# DVI-I.net
KiCad netlist of a schematic drawn in Altium Designer
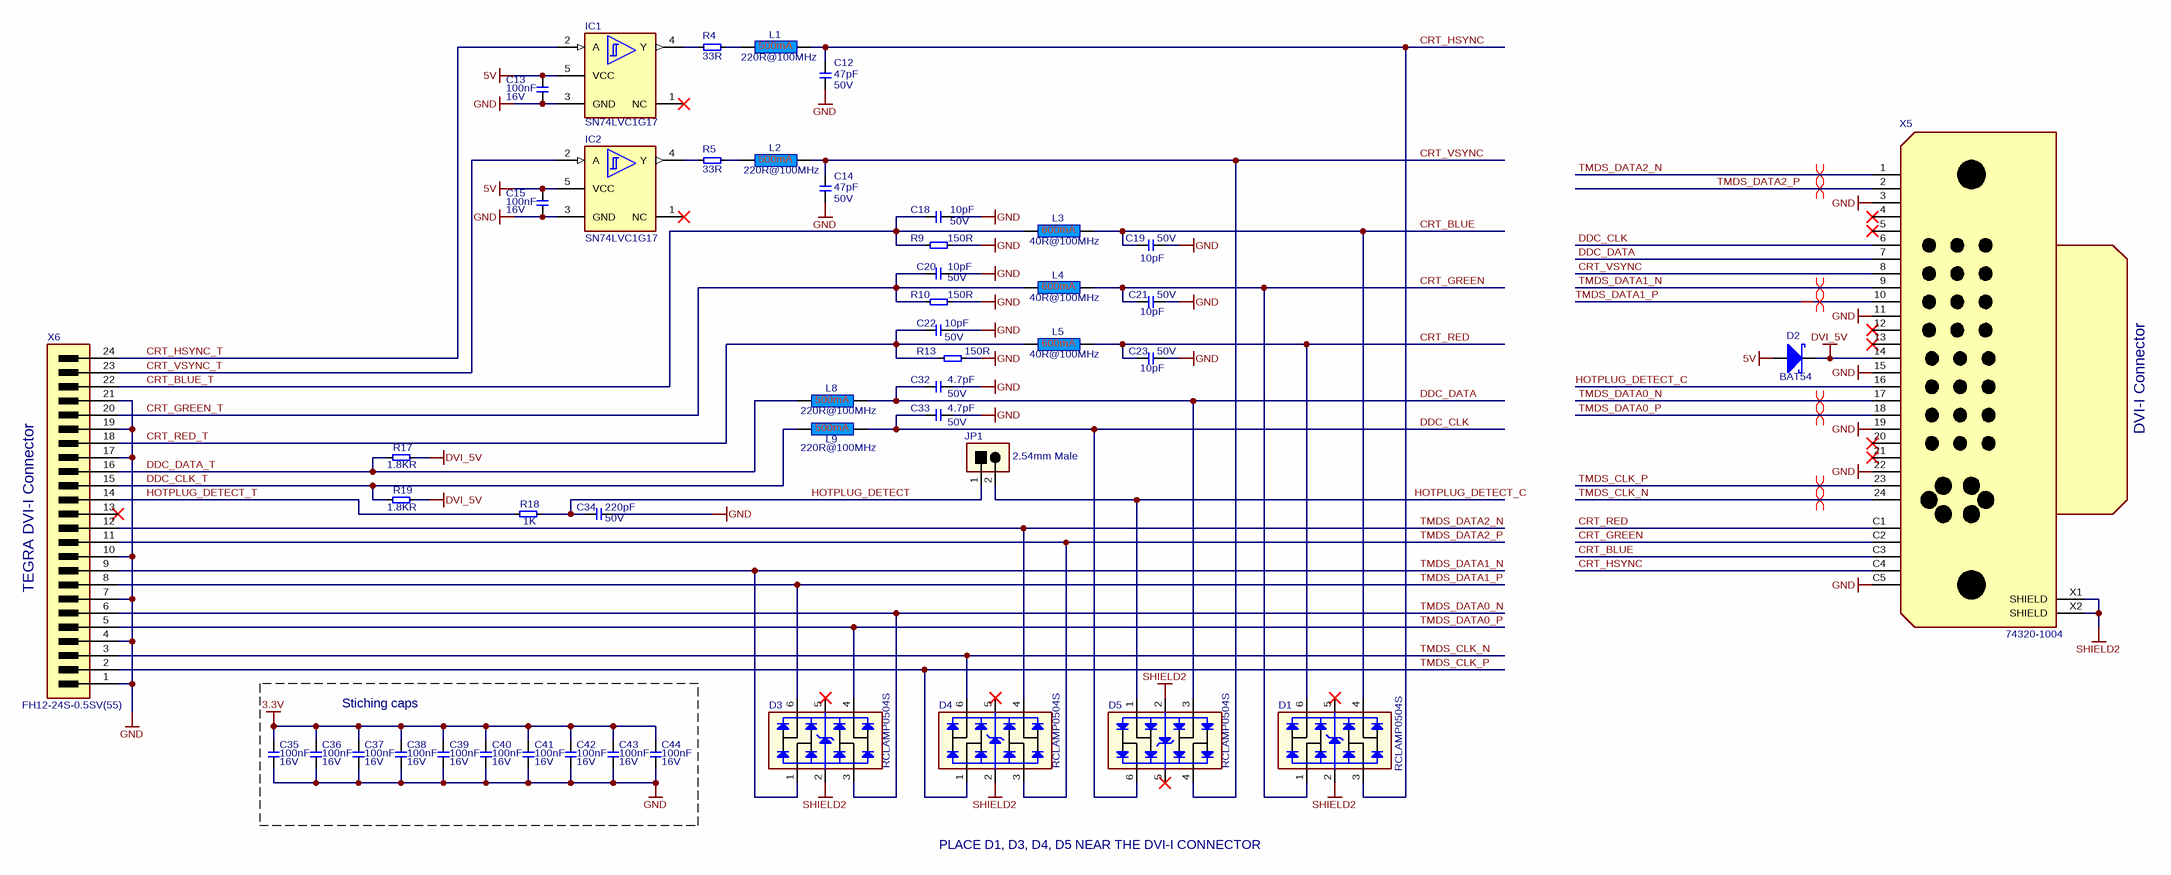
[diagram p0: DVI-I.SchDoc]

(export (version "E")
  (design (tool "Eeschema 10.0.6"))
  (components
    (comp (ref "C12")
      (value "47pF")
      (footprint "T_CAPC0603X33N")
      (description "Capacitor Ceramic NP0 47pF 50V 10% 0603")
      (fields (field (name "TOLERANCE") "10%") (field (name "RATING") "50V"))
      (libsource (lib "Evaluation Board") (part "C-NP0-47pF-50V-10%-0603"))
    )
    (comp (ref "C13")
      (value "100nF")
      (footprint "T_CAPC0603X33N")
      (description "Capacitor Ceramic X7R 100nF 16V 10% 0603")
      (fields (field (name "TOLERANCE") "10%") (field (name "RATING") "16V"))
      (libsource (lib "Evaluation Board") (part "C-X7R-100nF-16V-10%-0603"))
    )
    (comp (ref "C14")
      (value "47pF")
      (footprint "T_CAPC0603X33N")
      (description "Capacitor Ceramic NP0 47pF 50V 10% 0603")
      (fields (field (name "TOLERANCE") "10%") (field (name "RATING") "50V"))
      (libsource (lib "Evaluation Board") (part "C-NP0-47pF-50V-10%-0603"))
    )
    (comp (ref "C15")
      (value "100nF")
      (footprint "T_CAPC0603X33N")
      (description "Capacitor Ceramic X7R 100nF 16V 10% 0603")
      (fields (field (name "TOLERANCE") "10%") (field (name "RATING") "16V"))
      (libsource (lib "Evaluation Board") (part "C-X7R-100nF-16V-10%-0603"))
    )
    (comp (ref "C18")
      (value "10pF")
      (footprint "T_CAPC0603X33N")
      (description "Capacitor Ceramic NP0 10pF 50V 10% 0603")
      (fields (field (name "TOLERANCE") "10%") (field (name "RATING") "50V"))
      (libsource (lib "Evaluation Board") (part "C-NP0-10pF-50V-10%-0603"))
    )
    (comp (ref "C19")
      (value "10pF")
      (footprint "T_CAPC0603X33N")
      (description "Capacitor Ceramic NP0 10pF 50V 10% 0603")
      (fields (field (name "TOLERANCE") "10%") (field (name "RATING") "50V"))
      (libsource (lib "Evaluation Board") (part "C-NP0-10pF-50V-10%-0603"))
    )
    (comp (ref "C20")
      (value "10pF")
      (footprint "T_CAPC0603X33N")
      (description "Capacitor Ceramic NP0 10pF 50V 10% 0603")
      (fields (field (name "TOLERANCE") "10%") (field (name "RATING") "50V"))
      (libsource (lib "Evaluation Board") (part "C-NP0-10pF-50V-10%-0603"))
    )
    (comp (ref "C21")
      (value "10pF")
      (footprint "T_CAPC0603X33N")
      (description "Capacitor Ceramic NP0 10pF 50V 10% 0603")
      (fields (field (name "TOLERANCE") "10%") (field (name "RATING") "50V"))
      (libsource (lib "Evaluation Board") (part "C-NP0-10pF-50V-10%-0603"))
    )
    (comp (ref "C22")
      (value "10pF")
      (footprint "T_CAPC0603X33N")
      (description "Capacitor Ceramic NP0 10pF 50V 10% 0603")
      (fields (field (name "TOLERANCE") "10%") (field (name "RATING") "50V"))
      (libsource (lib "Evaluation Board") (part "C-NP0-10pF-50V-10%-0603"))
    )
    (comp (ref "C23")
      (value "10pF")
      (footprint "T_CAPC0603X33N")
      (description "Capacitor Ceramic NP0 10pF 50V 10% 0603")
      (fields (field (name "TOLERANCE") "10%") (field (name "RATING") "50V"))
      (libsource (lib "Evaluation Board") (part "C-NP0-10pF-50V-10%-0603"))
    )
    (comp (ref "C32")
      (value "4.7pF")
      (footprint "T_CAPC0603X33N")
      (description "Capacitor Ceramic NP0  4.7pF 25V 10% 0603")
      (fields (field (name "TOLERANCE") "10%") (field (name "RATING") "50V"))
      (libsource (lib "Evaluation Board") (part "C-NP0-4.7pF-25V-10%-0603"))
    )
    (comp (ref "C33")
      (value "4.7pF")
      (footprint "T_CAPC0603X33N")
      (description "Capacitor Ceramic NP0  4.7pF 25V 10% 0603")
      (fields (field (name "TOLERANCE") "10%") (field (name "RATING") "50V"))
      (libsource (lib "Evaluation Board") (part "C-NP0-4.7pF-25V-10%-0603"))
    )
    (comp (ref "C34")
      (value "220pF")
      (footprint "T_CAPC0603X33N")
      (description "Capacitor Ceramic X7R 220pF 50V 20% 0603")
      (fields (field (name "TOLERANCE") "20%") (field (name "RATING") "50V"))
      (libsource (lib "Evaluation Board") (part "C-X7R-220pF-50V-20%-0603"))
    )
    (comp (ref "C35")
      (value "100nF")
      (footprint "T_CAPC0603X33N")
      (description "Capacitor Ceramic X7R 100nF 16V 10% 0603")
      (fields (field (name "TOLERANCE") "10%") (field (name "RATING") "16V"))
      (libsource (lib "Evaluation Board") (part "C-X7R-100nF-16V-10%-0603"))
    )
    (comp (ref "C36")
      (value "100nF")
      (footprint "T_CAPC0603X33N")
      (description "Capacitor Ceramic X7R 100nF 16V 10% 0603")
      (fields (field (name "TOLERANCE") "10%") (field (name "RATING") "16V"))
      (libsource (lib "Evaluation Board") (part "C-X7R-100nF-16V-10%-0603"))
    )
    (comp (ref "C37")
      (value "100nF")
      (footprint "T_CAPC0603X33N")
      (description "Capacitor Ceramic X7R 100nF 16V 10% 0603")
      (fields (field (name "TOLERANCE") "10%") (field (name "RATING") "16V"))
      (libsource (lib "Evaluation Board") (part "C-X7R-100nF-16V-10%-0603"))
    )
    (comp (ref "C38")
      (value "100nF")
      (footprint "T_CAPC0603X33N")
      (description "Capacitor Ceramic X7R 100nF 16V 10% 0603")
      (fields (field (name "TOLERANCE") "10%") (field (name "RATING") "16V"))
      (libsource (lib "Evaluation Board") (part "C-X7R-100nF-16V-10%-0603"))
    )
    (comp (ref "C39")
      (value "100nF")
      (footprint "T_CAPC0603X33N")
      (description "Capacitor Ceramic X7R 100nF 16V 10% 0603")
      (fields (field (name "TOLERANCE") "10%") (field (name "RATING") "16V"))
      (libsource (lib "Evaluation Board") (part "C-X7R-100nF-16V-10%-0603"))
    )
    (comp (ref "C40")
      (value "100nF")
      (footprint "T_CAPC0603X33N")
      (description "Capacitor Ceramic X7R 100nF 16V 10% 0603")
      (fields (field (name "TOLERANCE") "10%") (field (name "RATING") "16V"))
      (libsource (lib "Evaluation Board") (part "C-X7R-100nF-16V-10%-0603"))
    )
    (comp (ref "C41")
      (value "100nF")
      (footprint "T_CAPC0603X33N")
      (description "Capacitor Ceramic X7R 100nF 16V 10% 0603")
      (fields (field (name "TOLERANCE") "10%") (field (name "RATING") "16V"))
      (libsource (lib "Evaluation Board") (part "C-X7R-100nF-16V-10%-0603"))
    )
    (comp (ref "C42")
      (value "100nF")
      (footprint "T_CAPC0603X33N")
      (description "Capacitor Ceramic X7R 100nF 16V 10% 0603")
      (fields (field (name "TOLERANCE") "10%") (field (name "RATING") "16V"))
      (libsource (lib "Evaluation Board") (part "C-X7R-100nF-16V-10%-0603"))
    )
    (comp (ref "C43")
      (value "100nF")
      (footprint "T_CAPC0603X33N")
      (description "Capacitor Ceramic X7R 100nF 16V 10% 0603")
      (fields (field (name "TOLERANCE") "10%") (field (name "RATING") "16V"))
      (libsource (lib "Evaluation Board") (part "C-X7R-100nF-16V-10%-0603"))
    )
    (comp (ref "C44")
      (value "100nF")
      (footprint "T_CAPC0603X33N")
      (description "Capacitor Ceramic X7R 100nF 16V 10% 0603")
      (fields (field (name "TOLERANCE") "10%") (field (name "RATING") "16V"))
      (libsource (lib "Evaluation Board") (part "C-X7R-100nF-16V-10%-0603"))
    )
    (comp (ref "D1")
      (value "RCLAMP0504S")
      (footprint "T_SOT95P285X90-6N")
      (description "TVS Array low cap")
      (fields (field (name "MANUFACTURER PART NO.") "RCLAMP0504S"))
      (libsource (lib "") (part "D-Semtech-RClamp0504S_1"))
    )
    (comp (ref "D2")
      (value "BAT54")
      (footprint "SOT95P230X110-3N")
      (description "BAT54 Schottky Diode")
      (fields (field (name "MANUFACTURER PART NO.") "BAT54"))
      (libsource (lib "Evaluation Board") (part "D-Philips-BAT54-Schottky"))
    )
    (comp (ref "D3")
      (value "RCLAMP0504S")
      (footprint "T_SOT95P285X90-6N")
      (description "TVS Array low cap")
      (fields (field (name "MANUFACTURER PART NO.") "RCLAMP0504S"))
      (libsource (lib "") (part "D-Semtech-RClamp0504S_1"))
    )
    (comp (ref "D4")
      (value "RCLAMP0504S")
      (footprint "T_SOT95P285X90-6N")
      (description "TVS Array low cap")
      (fields (field (name "MANUFACTURER PART NO.") "RCLAMP0504S"))
      (libsource (lib "") (part "D-Semtech-RClamp0504S_1"))
    )
    (comp (ref "D5")
      (value "RCLAMP0504S")
      (footprint "T_SOT95P285X90-6N")
      (description "TVS Array low cap")
      (fields (field (name "MANUFACTURER PART NO.") "RCLAMP0504S"))
      (libsource (lib "Evaluation Board") (part "D-Semtech-RClamp0504S"))
    )
    (comp (ref "IC1")
      (value "SN74LVC1G17")
      (footprint "SOT65P210X110-5N")
      (description "Single Schmitt-Trigger Buffer")
      (fields (field (name "MANUFACTURER PART NO.") "SN74LVC1G17"))
      (libsource (lib "Evaluation Board") (part "IC-TI-SN74LVC1G17"))
    )
    (comp (ref "IC2")
      (value "SN74LVC1G17")
      (footprint "SOT65P210X110-5N")
      (description "Single Schmitt-Trigger Buffer")
      (fields (field (name "MANUFACTURER PART NO.") "SN74LVC1G17"))
      (libsource (lib "Evaluation Board") (part "IC-TI-SN74LVC1G17"))
    )
    (comp (ref "JP1")
      (value "TSW-101-07-G-D")
      (footprint "T_Samtec_TSW-101-07-G-D")
      (description "Header male, 1x2 Pins, 2.54 mm pitch")
      (libsource (lib "Evaluation Board") (part "CON-Samtec-TSW-101-07-G-D"))
    )
    (comp (ref "L1")
      (value "220R@100MHz")
      (footprint "INDC1608X95N")
      (description "220R@100MHz 500mA EMI FILTER")
      (fields (field (name "TOLERANCE") "25%"))
      (libsource (lib "Evaluation Board") (part "L-220R@100MHz-500mA-25%-0603"))
    )
    (comp (ref "L2")
      (value "220R@100MHz")
      (footprint "INDC1608X95N")
      (description "220R@100MHz 500mA EMI FILTER")
      (fields (field (name "TOLERANCE") "25%"))
      (libsource (lib "Evaluation Board") (part "L-220R@100MHz-500mA-25%-0603"))
    )
    (comp (ref "L3")
      (value "40R@100MHz")
      (footprint "INDC1608X95N")
      (description "40R@100MHz 600mA EMI FILTER")
      (fields (field (name "TOLERANCE") "25%") (field (name "MANUFACTURER PART NO.") "MMZ1608S400A"))
      (libsource (lib "Evaluation Board") (part "L-TDK-MMZ1608S400A-40R@100MHz-600mA-25%-0603"))
    )
    (comp (ref "L4")
      (value "40R@100MHz")
      (footprint "INDC1608X95N")
      (description "40R@100MHz 600mA EMI FILTER")
      (fields (field (name "TOLERANCE") "25%") (field (name "MANUFACTURER PART NO.") "MMZ1608S400A"))
      (libsource (lib "Evaluation Board") (part "L-TDK-MMZ1608S400A-40R@100MHz-600mA-25%-0603"))
    )
    (comp (ref "L5")
      (value "40R@100MHz")
      (footprint "INDC1608X95N")
      (description "40R@100MHz 600mA EMI FILTER")
      (fields (field (name "TOLERANCE") "25%") (field (name "MANUFACTURER PART NO.") "MMZ1608S400A"))
      (libsource (lib "Evaluation Board") (part "L-TDK-MMZ1608S400A-40R@100MHz-600mA-25%-0603"))
    )
    (comp (ref "L8")
      (value "220R@100MHz")
      (footprint "INDC1608X95N")
      (description "220R@100MHz 500mA EMI FILTER")
      (fields (field (name "TOLERANCE") "25%"))
      (libsource (lib "Evaluation Board") (part "L-220R@100MHz-500mA-25%-0603"))
    )
    (comp (ref "L9")
      (value "220R@100MHz")
      (footprint "INDC1608X95N")
      (description "220R@100MHz 500mA EMI FILTER")
      (fields (field (name "TOLERANCE") "25%"))
      (libsource (lib "Evaluation Board") (part "L-220R@100MHz-500mA-25%-0603"))
    )
    (comp (ref "R4")
      (value "33R")
      (footprint "t_RESC0603X30N")
      (description "Resistor 33 ohm 63mW 5% 0603")
      (fields (field (name "TOLERANCE") "5%"))
      (libsource (lib "Evaluation Board") (part "R-33R-63mW-5%-0603"))
    )
    (comp (ref "R5")
      (value "33R")
      (footprint "t_RESC0603X30N")
      (description "Resistor 33 ohm 63mW 5% 0603")
      (fields (field (name "TOLERANCE") "5%"))
      (libsource (lib "Evaluation Board") (part "R-33R-63mW-5%-0603"))
    )
    (comp (ref "R9")
      (value "150R")
      (footprint "t_RESC0603X30N")
      (description "Resistor 150 ohm 63mW 1% 0603")
      (fields (field (name "TOLERANCE") "1%"))
      (libsource (lib "Evaluation Board") (part "R-150R-63mW-1%-0603"))
    )
    (comp (ref "R10")
      (value "150R")
      (footprint "t_RESC0603X30N")
      (description "Resistor 150 ohm 63mW 1% 0603")
      (fields (field (name "TOLERANCE") "1%"))
      (libsource (lib "Evaluation Board") (part "R-150R-63mW-1%-0603"))
    )
    (comp (ref "R13")
      (value "150R")
      (footprint "t_RESC0603X30N")
      (description "Resistor 150 ohm 63mW 1% 0603")
      (fields (field (name "TOLERANCE") "1%"))
      (libsource (lib "Evaluation Board") (part "R-150R-63mW-1%-0603"))
    )
    (comp (ref "R17")
      (value "1.8KR")
      (footprint "t_RESC0603X30N")
      (description "Resistor 1.8 Kohm 63mW 5% 0603")
      (fields (field (name "TOLERANCE") "5%") (field (name "Comment") "1.8K"))
      (libsource (lib "Evaluation Board") (part "R-1.8KR-63mW-5%-0603"))
    )
    (comp (ref "R18")
      (value "1K")
      (footprint "t_RESC0603X30N")
      (description "Resistor 1 Kohm 63mW 5% 0603")
      (fields (field (name "TOLERANCE") "5%"))
      (libsource (lib "Evaluation Board") (part "R-1KR-63mW-5%-0603"))
    )
    (comp (ref "R19")
      (value "1.8KR")
      (footprint "t_RESC0603X30N")
      (description "Resistor 1.8 Kohm 63mW 5% 0603")
      (fields (field (name "TOLERANCE") "5%") (field (name "Comment") "1.8K"))
      (libsource (lib "Evaluation Board") (part "R-1.8KR-63mW-5%-0603"))
    )
    (comp (ref "X5")
      (value "CON-Molex-74320-1004-31")
      (footprint "T_MOLEX_74320-1004")
      (description "DVI Connector")
      (fields (field (name "MANUFACTURER PART NO.") "74320-1004"))
      (libsource (lib "Evaluation Board") (part "CON-Molex-74320-1004-31"))
    )
    (comp (ref "X6")
      (value "FH12-24S-0.5SV(55)")
      (footprint "T_Hirose_FH12-24S-0.5SV(55)")
      (description "0.50mm Pitch FFC/FPC Vertical DVI Connector")
      (fields (field (name "MANUFACTURER PART NO.") "FH12-24S-0.5SV(55)"))
      (libsource (lib "Evaluation Board") (part "CON-Hirose-FH12-24S-0.5SV(55)-0.5mm"))
    )
  )
  (nets
    (net (code "1") (name "/CRT_BLUE") (class "Default")
      (node (ref "C19") (pin "1") (pinfunction "1_1") (pintype "passive"))
      (node (ref "D1") (pin "4") (pinfunction "4_4") (pintype "power_in"))
      (node (ref "L3") (pin "2") (pinfunction "2_2") (pintype "passive"))
      (node (ref "X5") (pin "C3") (pinfunction "CRT_BLUE_C3") (pintype "passive"))
    )
    (net (code "2") (name "/CRT_BLUE_T") (class "Default")
      (node (ref "C18") (pin "1") (pinfunction "1_1") (pintype "passive"))
      (node (ref "L3") (pin "1") (pinfunction "1_1") (pintype "passive"))
      (node (ref "R9") (pin "1") (pinfunction "1_1") (pintype "passive"))
      (node (ref "X6") (pin "22") (pinfunction "CRT_BLUE_22") (pintype "passive"))
    )
    (net (code "3") (name "/CRT_GREEN") (class "Default")
      (node (ref "C21") (pin "1") (pinfunction "1_1") (pintype "passive"))
      (node (ref "D1") (pin "1") (pinfunction "1_1") (pintype "power_in"))
      (node (ref "L4") (pin "2") (pinfunction "2_2") (pintype "passive"))
      (node (ref "X5") (pin "C2") (pinfunction "CRT_GREEN_C2") (pintype "passive"))
    )
    (net (code "4") (name "/CRT_GREEN_T") (class "Default")
      (node (ref "C20") (pin "1") (pinfunction "1_1") (pintype "passive"))
      (node (ref "L4") (pin "1") (pinfunction "1_1") (pintype "passive"))
      (node (ref "R10") (pin "1") (pinfunction "1_1") (pintype "passive"))
      (node (ref "X6") (pin "20") (pinfunction "CRT_GREEN_20") (pintype "passive"))
    )
    (net (code "5") (name "/CRT_HSYNC") (class "Default")
      (node (ref "C12") (pin "1") (pinfunction "1_1") (pintype "passive"))
      (node (ref "D1") (pin "3") (pinfunction "3_3") (pintype "power_in"))
      (node (ref "L1") (pin "2") (pinfunction "2_2") (pintype "passive"))
      (node (ref "X5") (pin "C4") (pinfunction "CRT_HSYNC_C4") (pintype "passive"))
    )
    (net (code "6") (name "/CRT_HSYNC_T") (class "Default")
      (node (ref "IC1") (pin "2") (pinfunction "A_2") (pintype "input"))
      (node (ref "X6") (pin "24") (pinfunction "CRT_HSYNC_24") (pintype "passive"))
    )
    (net (code "7") (name "/CRT_RED") (class "Default")
      (node (ref "C23") (pin "1") (pinfunction "1_1") (pintype "passive"))
      (node (ref "D1") (pin "6") (pinfunction "6_6") (pintype "power_in"))
      (node (ref "L5") (pin "2") (pinfunction "2_2") (pintype "passive"))
      (node (ref "X5") (pin "C1") (pinfunction "CRT_RED_C1") (pintype "passive"))
    )
    (net (code "8") (name "/CRT_RED_T") (class "Default")
      (node (ref "C22") (pin "1") (pinfunction "1_1") (pintype "passive"))
      (node (ref "L5") (pin "1") (pinfunction "1_1") (pintype "passive"))
      (node (ref "R13") (pin "1") (pinfunction "1_1") (pintype "passive"))
      (node (ref "X6") (pin "18") (pinfunction "CRT_RED_18") (pintype "passive"))
    )
    (net (code "9") (name "/CRT_VSYNC") (class "Default")
      (node (ref "C14") (pin "1") (pinfunction "1_1") (pintype "passive"))
      (node (ref "D5") (pin "4") (pinfunction "4_4") (pintype "power_in"))
      (node (ref "L2") (pin "2") (pinfunction "2_2") (pintype "passive"))
      (node (ref "X5") (pin "8") (pinfunction "CRT_VSYNC_8") (pintype "passive"))
    )
    (net (code "10") (name "/CRT_VSYNC_T") (class "Default")
      (node (ref "IC2") (pin "2") (pinfunction "A_2") (pintype "input"))
      (node (ref "X6") (pin "23") (pinfunction "CRT_VSYNC_23") (pintype "passive"))
    )
    (net (code "11") (name "/DDC_CLK") (class "Default")
      (node (ref "C33") (pin "1") (pinfunction "1_1") (pintype "passive"))
      (node (ref "D5") (pin "6") (pinfunction "6_6") (pintype "power_in"))
      (node (ref "L9") (pin "2") (pinfunction "2_2") (pintype "passive"))
      (node (ref "X5") (pin "6") (pinfunction "DDC_CLK_6") (pintype "passive"))
    )
    (net (code "12") (name "/DDC_CLK_T") (class "Default")
      (node (ref "L9") (pin "1") (pinfunction "1_1") (pintype "passive"))
      (node (ref "R19") (pin "2") (pinfunction "2_2") (pintype "passive"))
      (node (ref "X6") (pin "15") (pinfunction "DDC_CLK_15") (pintype "passive"))
    )
    (net (code "13") (name "/DDC_DATA") (class "Default")
      (node (ref "C32") (pin "1") (pinfunction "1_1") (pintype "passive"))
      (node (ref "D5") (pin "3") (pinfunction "3_3") (pintype "power_in"))
      (node (ref "L8") (pin "2") (pinfunction "2_2") (pintype "passive"))
      (node (ref "X5") (pin "7") (pinfunction "DDC_DATA_7") (pintype "passive"))
    )
    (net (code "14") (name "/DDC_DATA_T") (class "Default")
      (node (ref "L8") (pin "1") (pinfunction "1_1") (pintype "passive"))
      (node (ref "R17") (pin "2") (pinfunction "2_2") (pintype "passive"))
      (node (ref "X6") (pin "16") (pinfunction "DDC_DATA_16") (pintype "passive"))
    )
    (net (code "15") (name "/HOTPLUG_DETECT") (class "Default")
      (node (ref "C34") (pin "1") (pinfunction "1_1") (pintype "passive"))
      (node (ref "JP1") (pin "1") (pinfunction "1_1") (pintype "passive"))
      (node (ref "R18") (pin "2") (pinfunction "2_2") (pintype "passive"))
    )
    (net (code "16") (name "/HOTPLUG_DETECT_C") (class "Default")
      (node (ref "D5") (pin "1") (pinfunction "1_1") (pintype "power_in"))
      (node (ref "JP1") (pin "2") (pinfunction "2_2") (pintype "passive"))
      (node (ref "X5") (pin "16") (pinfunction "HOTPLUG_DETECT_16") (pintype "passive"))
    )
    (net (code "17") (name "/HOTPLUG_DETECT_T") (class "Default")
      (node (ref "R18") (pin "1") (pinfunction "1_1") (pintype "passive"))
      (node (ref "X6") (pin "14") (pinfunction "HOTPLUG_DETECT_14") (pintype "passive"))
    )
    (net (code "18") (name "/TMDS_CLK_N") (class "Default")
      (node (ref "D4") (pin "6") (pinfunction "6_6") (pintype "power_in"))
      (node (ref "X5") (pin "24") (pinfunction "TMDS_CLK_N_24") (pintype "passive"))
      (node (ref "X6") (pin "3") (pinfunction "TMDS_CLK_N_3") (pintype "passive"))
    )
    (net (code "19") (name "/TMDS_CLK_P") (class "Default")
      (node (ref "D4") (pin "1") (pinfunction "1_1") (pintype "power_in"))
      (node (ref "X5") (pin "23") (pinfunction "TMDS_CLK_P_23") (pintype "passive"))
      (node (ref "X6") (pin "2") (pinfunction "TMDS_CLK_P_2") (pintype "passive"))
    )
    (net (code "20") (name "/TMDS_DATA0_N") (class "Default")
      (node (ref "D3") (pin "3") (pinfunction "3_3") (pintype "power_in"))
      (node (ref "X5") (pin "17") (pinfunction "TMDS_DATA0_N_17") (pintype "passive"))
      (node (ref "X6") (pin "6") (pinfunction "TMDS_DATA0_N_6") (pintype "passive"))
    )
    (net (code "21") (name "/TMDS_DATA0_P") (class "Default")
      (node (ref "D3") (pin "4") (pinfunction "4_4") (pintype "power_in"))
      (node (ref "X5") (pin "18") (pinfunction "TMDS_DATA0_P_18") (pintype "passive"))
      (node (ref "X6") (pin "5") (pinfunction "TMDS_DATA0_P_5") (pintype "passive"))
    )
    (net (code "22") (name "/TMDS_DATA1_N") (class "Default")
      (node (ref "D3") (pin "1") (pinfunction "1_1") (pintype "power_in"))
      (node (ref "X5") (pin "9") (pinfunction "TMDS_DATA1_N_9") (pintype "passive"))
      (node (ref "X6") (pin "9") (pinfunction "TMDS_DATA1_N_9") (pintype "passive"))
    )
    (net (code "23") (name "/TMDS_DATA1_P") (class "Default")
      (node (ref "D3") (pin "6") (pinfunction "6_6") (pintype "power_in"))
      (node (ref "X5") (pin "10") (pinfunction "TMDS_DATA1_P_10") (pintype "passive"))
      (node (ref "X6") (pin "8") (pinfunction "TMDS_DATA1_P_8") (pintype "passive"))
    )
    (net (code "24") (name "/TMDS_DATA2_N") (class "Default")
      (node (ref "D4") (pin "4") (pinfunction "4_4") (pintype "power_in"))
      (node (ref "X5") (pin "1") (pinfunction "TMDS_DATA2_N_1") (pintype "passive"))
      (node (ref "X6") (pin "12") (pinfunction "TMDS_DATA2_N_12") (pintype "passive"))
    )
    (net (code "25") (name "/TMDS_DATA2_P") (class "Default")
      (node (ref "D4") (pin "3") (pinfunction "3_3") (pintype "power_in"))
      (node (ref "X5") (pin "2") (pinfunction "TMDS_DATA2_P_2") (pintype "passive"))
      (node (ref "X6") (pin "11") (pinfunction "TMDS_DATA2_P_11") (pintype "passive"))
    )
    (net (code "26") (name "3.3V") (class "Default")
      (node (ref "C35") (pin "2") (pinfunction "2_2") (pintype "passive"))
      (node (ref "C36") (pin "2") (pinfunction "2_2") (pintype "passive"))
      (node (ref "C37") (pin "2") (pinfunction "2_2") (pintype "passive"))
      (node (ref "C38") (pin "2") (pinfunction "2_2") (pintype "passive"))
      (node (ref "C39") (pin "2") (pinfunction "2_2") (pintype "passive"))
      (node (ref "C40") (pin "2") (pinfunction "2_2") (pintype "passive"))
      (node (ref "C41") (pin "2") (pinfunction "2_2") (pintype "passive"))
      (node (ref "C42") (pin "2") (pinfunction "2_2") (pintype "passive"))
      (node (ref "C43") (pin "2") (pinfunction "2_2") (pintype "passive"))
      (node (ref "C44") (pin "2") (pinfunction "2_2") (pintype "passive"))
    )
    (net (code "27") (name "5V") (class "Default")
      (node (ref "C13") (pin "2") (pinfunction "2_2") (pintype "passive"))
      (node (ref "C15") (pin "2") (pinfunction "2_2") (pintype "passive"))
      (node (ref "D2") (pin "1") (pinfunction "1_1") (pintype "passive"))
      (node (ref "IC1") (pin "5") (pinfunction "VCC_5") (pintype "power_in"))
      (node (ref "IC2") (pin "5") (pinfunction "VCC_5") (pintype "power_in"))
    )
    (net (code "28") (name "DVI_5V") (class "Default")
      (node (ref "D2") (pin "3") (pinfunction "3_3") (pintype "passive"))
      (node (ref "R17") (pin "1") (pinfunction "1_1") (pintype "passive"))
      (node (ref "R19") (pin "1") (pinfunction "1_1") (pintype "passive"))
      (node (ref "X5") (pin "14") (pinfunction "VDD_DVI_14") (pintype "passive"))
    )
    (net (code "29") (name "GND") (class "Default")
      (node (ref "C12") (pin "2") (pinfunction "2_2") (pintype "passive"))
      (node (ref "C13") (pin "1") (pinfunction "1_1") (pintype "passive"))
      (node (ref "C14") (pin "2") (pinfunction "2_2") (pintype "passive"))
      (node (ref "C15") (pin "1") (pinfunction "1_1") (pintype "passive"))
      (node (ref "C18") (pin "2") (pinfunction "2_2") (pintype "passive"))
      (node (ref "C19") (pin "2") (pinfunction "2_2") (pintype "passive"))
      (node (ref "C20") (pin "2") (pinfunction "2_2") (pintype "passive"))
      (node (ref "C21") (pin "2") (pinfunction "2_2") (pintype "passive"))
      (node (ref "C22") (pin "2") (pinfunction "2_2") (pintype "passive"))
      (node (ref "C23") (pin "2") (pinfunction "2_2") (pintype "passive"))
      (node (ref "C32") (pin "2") (pinfunction "2_2") (pintype "passive"))
      (node (ref "C33") (pin "2") (pinfunction "2_2") (pintype "passive"))
      (node (ref "C34") (pin "2") (pinfunction "2_2") (pintype "passive"))
      (node (ref "C35") (pin "1") (pinfunction "1_1") (pintype "passive"))
      (node (ref "C36") (pin "1") (pinfunction "1_1") (pintype "passive"))
      (node (ref "C37") (pin "1") (pinfunction "1_1") (pintype "passive"))
      (node (ref "C38") (pin "1") (pinfunction "1_1") (pintype "passive"))
      (node (ref "C39") (pin "1") (pinfunction "1_1") (pintype "passive"))
      (node (ref "C40") (pin "1") (pinfunction "1_1") (pintype "passive"))
      (node (ref "C41") (pin "1") (pinfunction "1_1") (pintype "passive"))
      (node (ref "C42") (pin "1") (pinfunction "1_1") (pintype "passive"))
      (node (ref "C43") (pin "1") (pinfunction "1_1") (pintype "passive"))
      (node (ref "C44") (pin "1") (pinfunction "1_1") (pintype "passive"))
      (node (ref "IC1") (pin "3") (pinfunction "GND_3") (pintype "power_in"))
      (node (ref "IC2") (pin "3") (pinfunction "GND_3") (pintype "power_in"))
      (node (ref "R10") (pin "2") (pinfunction "2_2") (pintype "passive"))
      (node (ref "R13") (pin "2") (pinfunction "2_2") (pintype "passive"))
      (node (ref "R9") (pin "2") (pinfunction "2_2") (pintype "passive"))
      (node (ref "X5") (pin "11") (pinfunction "GND_11") (pintype "passive"))
      (node (ref "X5") (pin "15") (pinfunction "GND_15") (pintype "passive"))
      (node (ref "X5") (pin "19") (pinfunction "GND_19") (pintype "passive"))
      (node (ref "X5") (pin "22") (pinfunction "GND_22") (pintype "passive"))
      (node (ref "X5") (pin "3") (pinfunction "GND_3") (pintype "passive"))
      (node (ref "X5") (pin "C5") (pinfunction "GND_C5") (pintype "passive"))
      (node (ref "X6") (pin "1") (pinfunction "GND_1") (pintype "passive"))
      (node (ref "X6") (pin "10") (pinfunction "GND_10") (pintype "passive"))
      (node (ref "X6") (pin "17") (pinfunction "GND_17") (pintype "passive"))
      (node (ref "X6") (pin "19") (pinfunction "GND_19") (pintype "passive"))
      (node (ref "X6") (pin "21") (pinfunction "GND_21") (pintype "passive"))
      (node (ref "X6") (pin "4") (pinfunction "GND_4") (pintype "passive"))
      (node (ref "X6") (pin "7") (pinfunction "GND_7") (pintype "passive"))
    )
    (net (code "30") (name "Net-(IC1-Y)") (class "Default")
      (node (ref "IC1") (pin "4") (pinfunction "Y_4") (pintype "output"))
      (node (ref "R4") (pin "1") (pinfunction "1_1") (pintype "passive"))
    )
    (net (code "31") (name "Net-(IC2-Y)") (class "Default")
      (node (ref "IC2") (pin "4") (pinfunction "Y_4") (pintype "output"))
      (node (ref "R5") (pin "1") (pinfunction "1_1") (pintype "passive"))
    )
    (net (code "32") (name "Net-(L1-Pad1)") (class "Default")
      (node (ref "L1") (pin "1") (pinfunction "1_1") (pintype "passive"))
      (node (ref "R4") (pin "2") (pinfunction "2_2") (pintype "passive"))
    )
    (net (code "33") (name "Net-(L2-Pad1)") (class "Default")
      (node (ref "L2") (pin "1") (pinfunction "1_1") (pintype "passive"))
      (node (ref "R5") (pin "2") (pinfunction "2_2") (pintype "passive"))
    )
    (net (code "34") (name "SHIELD2") (class "Default")
      (node (ref "D1") (pin "2") (pinfunction "2_2") (pintype "power_in"))
      (node (ref "D3") (pin "2") (pinfunction "2_2") (pintype "power_in"))
      (node (ref "D4") (pin "2") (pinfunction "2_2") (pintype "power_in"))
      (node (ref "D5") (pin "2") (pinfunction "2_2") (pintype "power_in"))
      (node (ref "X5") (pin "X1") (pinfunction "SHIELD_X1") (pintype "passive"))
      (node (ref "X5") (pin "X2") (pinfunction "SHIELD_X2") (pintype "passive"))
    )
    (net (code "35") (name "unconnected-(D1-Pad5)") (class "Default")
      (node (ref "D1") (pin "5") (pinfunction "5_5") (pintype "power_in+no_connect"))
    )
    (net (code "36") (name "unconnected-(D3-Pad5)") (class "Default")
      (node (ref "D3") (pin "5") (pinfunction "5_5") (pintype "power_in+no_connect"))
    )
    (net (code "37") (name "unconnected-(D4-Pad5)") (class "Default")
      (node (ref "D4") (pin "5") (pinfunction "5_5") (pintype "power_in+no_connect"))
    )
    (net (code "38") (name "unconnected-(D5-Pad5)") (class "Default")
      (node (ref "D5") (pin "5") (pinfunction "5_5") (pintype "power_in+no_connect"))
    )
    (net (code "39") (name "unconnected-(IC1-NC-Pad1)") (class "Default")
      (node (ref "IC1") (pin "1") (pinfunction "NC_1") (pintype "passive+no_connect"))
    )
    (net (code "40") (name "unconnected-(IC2-NC-Pad1)") (class "Default")
      (node (ref "IC2") (pin "1") (pinfunction "NC_1") (pintype "passive+no_connect"))
    )
    (net (code "41") (name "unconnected-(X5-TMDS_DATA3_N-Pad12)") (class "Default")
      (node (ref "X5") (pin "12") (pinfunction "TMDS_DATA3_N_12") (pintype "passive+no_connect"))
    )
    (net (code "42") (name "unconnected-(X5-TMDS_DATA3_P-Pad13)") (class "Default")
      (node (ref "X5") (pin "13") (pinfunction "TMDS_DATA3_P_13") (pintype "passive+no_connect"))
    )
    (net (code "43") (name "unconnected-(X5-TMDS_DATA4_N-Pad4)") (class "Default")
      (node (ref "X5") (pin "4") (pinfunction "TMDS_DATA4_N_4") (pintype "passive+no_connect"))
    )
    (net (code "44") (name "unconnected-(X5-TMDS_DATA4_P-Pad5)") (class "Default")
      (node (ref "X5") (pin "5") (pinfunction "TMDS_DATA4_P_5") (pintype "passive+no_connect"))
    )
    (net (code "45") (name "unconnected-(X5-TMDS_DATA5_N-Pad20)") (class "Default")
      (node (ref "X5") (pin "20") (pinfunction "TMDS_DATA5_N_20") (pintype "passive+no_connect"))
    )
    (net (code "46") (name "unconnected-(X5-TMDS_DATA5_P-Pad21)") (class "Default")
      (node (ref "X5") (pin "21") (pinfunction "TMDS_DATA5_P_21") (pintype "passive+no_connect"))
    )
    (net (code "47") (name "unconnected-(X6-VDD-Pad13)") (class "Default")
      (node (ref "X6") (pin "13") (pinfunction "VDD_13") (pintype "passive+no_connect"))
    )
  )
)
